# Oszillator.net
KiCad netlist of a schematic drawn in Altium Designer
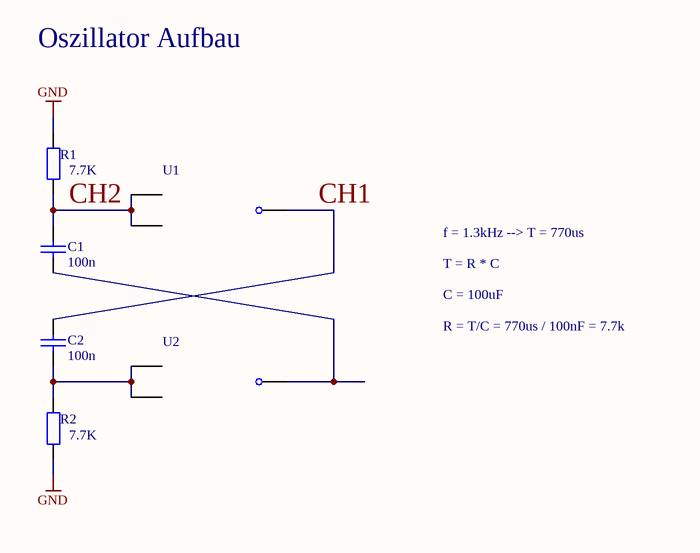
[diagram p0: Oszillator.SchDoc]

(export (version "E")
  (design (tool "Eeschema 10.0.6"))
  (components
    (comp (ref "C1")
      (value "100n")
      (description "Capacitor")
      (libsource (lib "Simulation Generic Components") (part "Capacitor"))
    )
    (comp (ref "C2")
      (value "100n")
      (description "Capacitor")
      (libsource (lib "Simulation Generic Components") (part "Capacitor"))
    )
    (comp (ref "R1")
      (value "7.7K")
      (footprint "AXIAL-0.4")
      (description "Resistor")
      (fields (field (name "Comment") "Res2") (field (name "PUBLISHER") "Altium Limited"))
      (libsource (lib "") (part "Res2_1"))
    )
    (comp (ref "R2")
      (value "7.7K")
      (footprint "AXIAL-0.4")
      (description "Resistor")
      (fields (field (name "Comment") "Res2") (field (name "PUBLISHER") "Altium Limited"))
      (libsource (lib "Miscellaneous Devices") (part "Res2"))
    )
    (comp (ref "U1")
      (value "Digital NAND Gate")
      (libsource (lib "Simulation Generic Components") (part "Digital NAND"))
    )
    (comp (ref "U2")
      (value "Digital NAND Gate")
      (libsource (lib "Simulation Generic Components") (part "Digital NAND"))
    )
  )
  (nets
    (net (code "1") (name "/CH1") (class "Default")
      (node (ref "C2") (pin "1") (pinfunction "1_1") (pintype "passive"))
      (node (ref "U1") (pin "3") (pinfunction "3_3") (pintype "passive"))
    )
    (net (code "2") (name "/CH2") (class "Default")
      (node (ref "C1") (pin "2") (pinfunction "2_2") (pintype "passive"))
      (node (ref "R1") (pin "1") (pinfunction "1_1") (pintype "passive"))
      (node (ref "U1") (pin "1") (pinfunction "1_1") (pintype "passive"))
      (node (ref "U1") (pin "2") (pinfunction "2_2") (pintype "passive"))
    )
    (net (code "3") (name "GND") (class "Default")
      (node (ref "R1") (pin "2") (pinfunction "2_2") (pintype "passive"))
      (node (ref "R2") (pin "2") (pinfunction "2_2") (pintype "passive"))
    )
    (net (code "4") (name "Net-(C1-Pad1)") (class "Default")
      (node (ref "C1") (pin "1") (pinfunction "1_1") (pintype "passive"))
      (node (ref "U2") (pin "3") (pinfunction "3_3") (pintype "passive"))
    )
    (net (code "5") (name "Net-(C2-Pad2)") (class "Default")
      (node (ref "C2") (pin "2") (pinfunction "2_2") (pintype "passive"))
      (node (ref "R2") (pin "1") (pinfunction "1_1") (pintype "passive"))
      (node (ref "U2") (pin "1") (pinfunction "1_1") (pintype "passive"))
      (node (ref "U2") (pin "2") (pinfunction "2_2") (pintype "passive"))
    )
  )
)
